# BTConnecter.net
KiCad netlist of a schematic drawn in Altium Designer
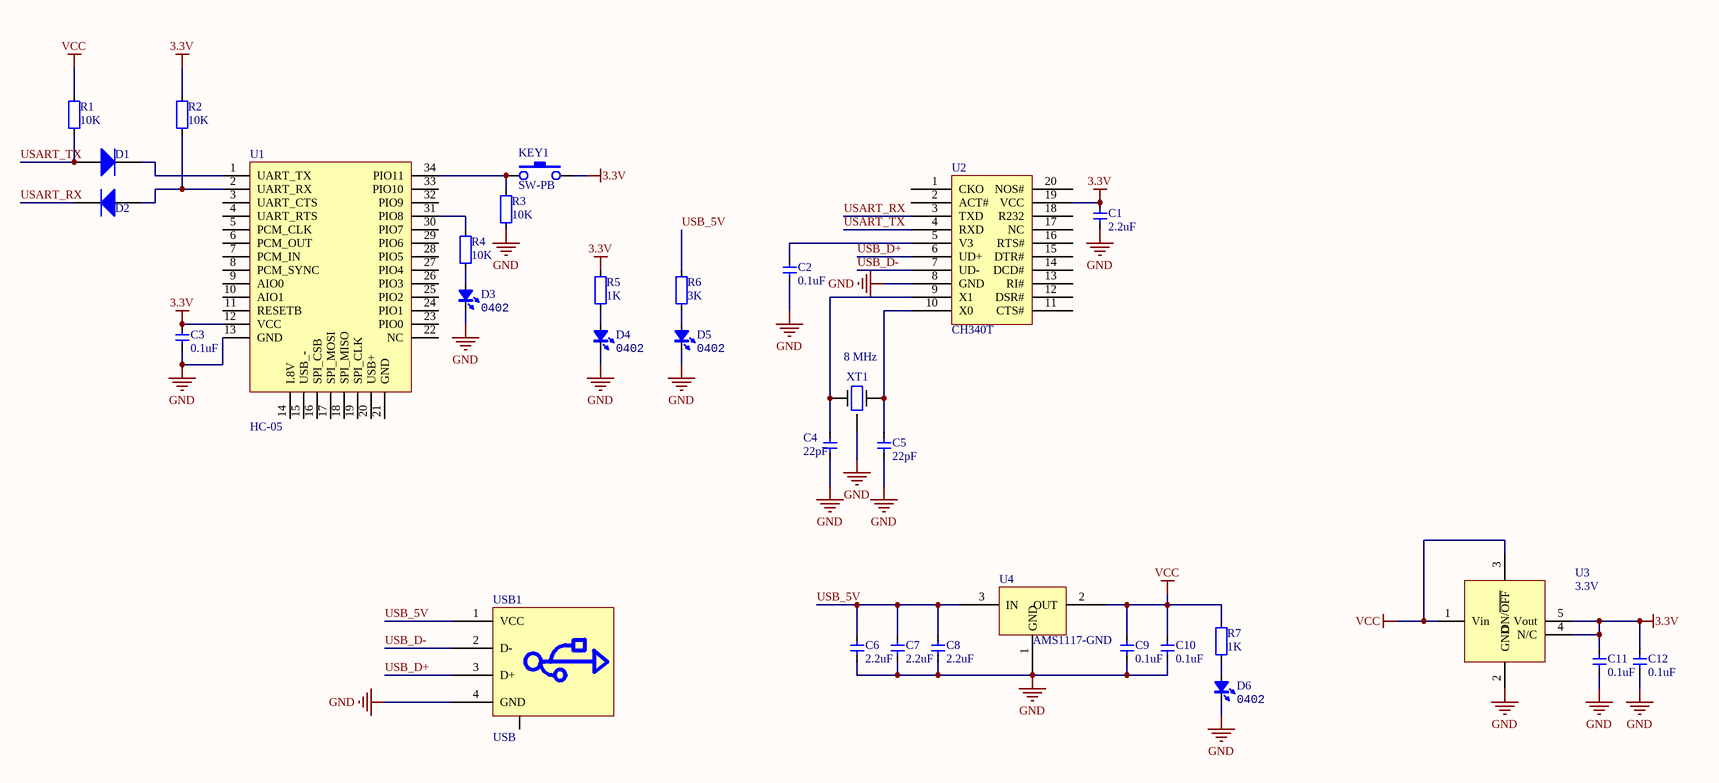
[diagram p0: BTConnecter.SchDoc]

(export (version "E")
  (design (tool "Eeschema 10.0.6"))
  (components
    (comp (ref "C1")
      (value "2.2uF")
      (footprint "CAP_0402")
      (description "Capacitor")
      (libsource (lib "BTConnecter") (part "电容-0402"))
    )
    (comp (ref "C2")
      (value "0.1uF")
      (footprint "CAP_0402")
      (description "Capacitor")
      (libsource (lib "BTConnecter") (part "电容-0402"))
    )
    (comp (ref "C3")
      (value "0.1uF")
      (footprint "CAP_0402")
      (description "Capacitor")
      (libsource (lib "BTConnecter") (part "电容-0402"))
    )
    (comp (ref "C4")
      (value "22pF")
      (footprint "CAP_0402")
      (description "Capacitor")
      (libsource (lib "BTConnecter") (part "电容-0402"))
    )
    (comp (ref "C5")
      (value "22pF")
      (footprint "CAP_0402")
      (description "Capacitor")
      (libsource (lib "BTConnecter") (part "电容-0402"))
    )
    (comp (ref "C6")
      (value "2.2uF")
      (footprint "CAP_0603")
      (description "Capacitor")
      (libsource (lib "BTConnecter") (part "电容-0603"))
    )
    (comp (ref "C7")
      (value "2.2uF")
      (footprint "CAP_0603")
      (description "Capacitor")
      (libsource (lib "BTConnecter") (part "电容-0603"))
    )
    (comp (ref "C8")
      (value "2.2uF")
      (footprint "CAP_0603")
      (description "Capacitor")
      (libsource (lib "BTConnecter") (part "电容-0603"))
    )
    (comp (ref "C9")
      (value "0.1uF")
      (footprint "CAP_0402")
      (description "Capacitor")
      (libsource (lib "BTConnecter") (part "电容-0402"))
    )
    (comp (ref "C10")
      (value "0.1uF")
      (footprint "CAP_0402")
      (description "Capacitor")
      (libsource (lib "BTConnecter") (part "电容-0402"))
    )
    (comp (ref "C11")
      (value "0.1uF")
      (footprint "CAP_0402")
      (description "Capacitor")
      (libsource (lib "BTConnecter") (part "电容-0402"))
    )
    (comp (ref "C12")
      (value "0.1uF")
      (footprint "CAP_0402")
      (description "Capacitor")
      (libsource (lib "BTConnecter") (part "电容-0402"))
    )
    (comp (ref "D1")
      (value "MBR140SFT1G")
      (footprint "DIOM2717X10N")
      (description "Rectifier Diode, Single, 40 V, 1 A, SOD-123FL, 2, 550 mV")
      (libsource (lib "BTConnecter") (part "MBR140SFT1G"))
    )
    (comp (ref "D2")
      (value "MBR140SFT1G")
      (footprint "DIOM2717X10N")
      (description "Rectifier Diode, Single, 40 V, 1 A, SOD-123FL, 2, 550 mV")
      (libsource (lib "BTConnecter") (part "MBR140SFT1G"))
    )
    (comp (ref "D3")
      (value "color?")
      (footprint "LED_0402")
      (description "LED")
      (fields (field (name "TYPE") "0402"))
      (libsource (lib "BTConnecter") (part "LED_0402"))
    )
    (comp (ref "D4")
      (value "color?")
      (footprint "LED_0402")
      (description "LED")
      (fields (field (name "TYPE") "0402"))
      (libsource (lib "BTConnecter") (part "LED_0402"))
    )
    (comp (ref "D5")
      (value "color?")
      (footprint "LED_0402")
      (description "LED")
      (fields (field (name "TYPE") "0402"))
      (libsource (lib "BTConnecter") (part "LED_0402"))
    )
    (comp (ref "D6")
      (value "color?")
      (footprint "LED_0402")
      (description "LED")
      (fields (field (name "TYPE") "0402"))
      (libsource (lib "BTConnecter") (part "LED_0402"))
    )
    (comp (ref "KEY1")
      (value "SW-PB")
      (footprint "ButtonTACT_3x4x2_180H")
      (libsource (lib "BTConnecter") (part "KEY"))
    )
    (comp (ref "R1")
      (value "10K")
      (footprint "RES_0402")
      (description "Resistor")
      (libsource (lib "BTConnecter") (part "电阻-0402"))
    )
    (comp (ref "R2")
      (value "10K")
      (footprint "RES_0402")
      (description "Resistor")
      (libsource (lib "BTConnecter") (part "电阻-0402"))
    )
    (comp (ref "R3")
      (value "10K")
      (footprint "RES_0402")
      (description "Resistor")
      (libsource (lib "BTConnecter") (part "电阻-0402"))
    )
    (comp (ref "R4")
      (value "10K")
      (footprint "RES_0402")
      (description "Resistor")
      (libsource (lib "BTConnecter") (part "电阻-0402"))
    )
    (comp (ref "R5")
      (value "1K")
      (footprint "RES_0402")
      (description "Resistor")
      (libsource (lib "BTConnecter") (part "电阻-0402"))
    )
    (comp (ref "R6")
      (value "3K")
      (footprint "RES_0402")
      (description "Resistor")
      (libsource (lib "BTConnecter") (part "电阻-0402"))
    )
    (comp (ref "R7")
      (value "1K")
      (footprint "RES_0402")
      (description "Resistor")
      (libsource (lib "BTConnecter") (part "电阻-0402"))
    )
    (comp (ref "U1")
      (value "HC-05")
      (footprint "HC-05/06/08V15")
      (libsource (lib "BTConnecter") (part "蓝牙hc05"))
    )
    (comp (ref "U2")
      (value "CH340T")
      (footprint "SSOP-20")
      (description "Port")
      (libsource (lib "BTConnecter") (part "CH340T"))
    )
    (comp (ref "U3")
      (value "3.3V")
      (footprint "SOT23-5")
      (description "IC REG LDO 3.3V 0.25A SOT23-5")
      (fields (field (name "MANUFACTURER") "Texas Instruments"))
      (libsource (lib "BTConnecter") (part "LP5907MFX-3.3/NOPB"))
    )
    (comp (ref "U4")
      (value "AMS1117-GND")
      (footprint "SOT223_JX")
      (description "IC")
      (libsource (lib "BTConnecter") (part "AMS1117-GND"))
    )
    (comp (ref "USB1") (value "USB") (footprint "USB-plug1") (libsource (lib "BTConnecter") (part "USB公头")))
    (comp (ref "XT1")
      (value "8 MHz")
      (footprint "DFN220P320X110-4N")
      (description "Crystal 8MHz ±10ppm 10pF 200 Ohm -10°C ~ 60°C Surface Mount 4-SMD, No Lead (DFN, LCC)")
      (fields
        (field (name "MANUFACTURER") "Abracon LLC")
        (field (name "MANUFACTURER PART NUMBER") "ABM3B-8.000MHZ-10-1-U-T")
      )
      (libsource (lib "BTConnecter") (part "ABM3B-8.000MHZ-10-1-U-T"))
    )
  )
  (nets
    (net (code "1") (name "/USART_RX") (class "Default")
      (node (ref "D2") (pin "K") (pinfunction "K_K") (pintype "passive"))
      (node (ref "U2") (pin "3") (pinfunction "TXD_3") (pintype "passive"))
    )
    (net (code "2") (name "/USART_TX") (class "Default")
      (node (ref "D1") (pin "A") (pinfunction "A_A") (pintype "passive"))
      (node (ref "R1") (pin "1") (pinfunction "1_1") (pintype "passive"))
      (node (ref "U2") (pin "4") (pinfunction "RXD_4") (pintype "passive"))
    )
    (net (code "3") (name "/USB_5V") (class "Default")
      (node (ref "C6") (pin "2") (pinfunction "2_2") (pintype "passive"))
      (node (ref "C7") (pin "2") (pinfunction "2_2") (pintype "passive"))
      (node (ref "C8") (pin "1") (pinfunction "1_1") (pintype "passive"))
      (node (ref "R6") (pin "2") (pinfunction "2_2") (pintype "passive"))
      (node (ref "U4") (pin "3") (pinfunction "IN_3") (pintype "passive"))
      (node (ref "USB1") (pin "1") (pinfunction "VCC_1") (pintype "passive"))
    )
    (net (code "4") (name "/USB_D+") (class "Default")
      (node (ref "U2") (pin "6") (pinfunction "UD+_6") (pintype "passive"))
      (node (ref "USB1") (pin "3") (pinfunction "D+_3") (pintype "passive"))
    )
    (net (code "5") (name "/USB_D-") (class "Default")
      (node (ref "U2") (pin "7") (pinfunction "UD-_7") (pintype "passive"))
      (node (ref "USB1") (pin "2") (pinfunction "D-_2") (pintype "passive"))
    )
    (net (code "6") (name "3.3V") (class "Default")
      (node (ref "C1") (pin "2") (pinfunction "2_2") (pintype "passive"))
      (node (ref "C11") (pin "2") (pinfunction "2_2") (pintype "passive"))
      (node (ref "C12") (pin "2") (pinfunction "2_2") (pintype "passive"))
      (node (ref "C3") (pin "2") (pinfunction "2_2") (pintype "passive"))
      (node (ref "KEY1") (pin "2") (pintype "passive"))
      (node (ref "R2") (pin "2") (pinfunction "2_2") (pintype "passive"))
      (node (ref "R5") (pin "2") (pinfunction "2_2") (pintype "passive"))
      (node (ref "U1") (pin "12") (pinfunction "VCC_12") (pintype "passive"))
      (node (ref "U2") (pin "19") (pinfunction "VCC_19") (pintype "passive"))
      (node (ref "U3") (pin "4") (pinfunction "N/C_4") (pintype "passive"))
      (node (ref "U3") (pin "5") (pinfunction "Vout_5") (pintype "passive"))
    )
    (net (code "7") (name "GND") (class "Default")
      (node (ref "C1") (pin "1") (pinfunction "1_1") (pintype "passive"))
      (node (ref "C10") (pin "1") (pinfunction "1_1") (pintype "passive"))
      (node (ref "C11") (pin "1") (pinfunction "1_1") (pintype "passive"))
      (node (ref "C12") (pin "1") (pinfunction "1_1") (pintype "passive"))
      (node (ref "C2") (pin "1") (pinfunction "1_1") (pintype "passive"))
      (node (ref "C3") (pin "1") (pinfunction "1_1") (pintype "passive"))
      (node (ref "C4") (pin "1") (pinfunction "1_1") (pintype "passive"))
      (node (ref "C5") (pin "1") (pinfunction "1_1") (pintype "passive"))
      (node (ref "C6") (pin "1") (pinfunction "1_1") (pintype "passive"))
      (node (ref "C7") (pin "1") (pinfunction "1_1") (pintype "passive"))
      (node (ref "C8") (pin "2") (pinfunction "2_2") (pintype "passive"))
      (node (ref "C9") (pin "1") (pinfunction "1_1") (pintype "passive"))
      (node (ref "D3") (pin "2") (pinfunction "K_2") (pintype "passive"))
      (node (ref "D4") (pin "2") (pinfunction "K_2") (pintype "passive"))
      (node (ref "D5") (pin "2") (pinfunction "K_2") (pintype "passive"))
      (node (ref "D6") (pin "2") (pinfunction "K_2") (pintype "passive"))
      (node (ref "R3") (pin "1") (pinfunction "1_1") (pintype "passive"))
      (node (ref "U1") (pin "13") (pinfunction "GND_13") (pintype "passive"))
      (node (ref "U2") (pin "8") (pinfunction "GND_8") (pintype "passive"))
      (node (ref "U3") (pin "2") (pinfunction "GND_2") (pintype "passive"))
      (node (ref "U4") (pin "1") (pinfunction "GND_1") (pintype "passive"))
      (node (ref "USB1") (pin "4") (pinfunction "GND_4") (pintype "passive"))
      (node (ref "XT1") (pin "G") (pintype "passive"))
    )
    (net (code "8") (name "Net-(D3-A)") (class "Default")
      (node (ref "D3") (pin "1") (pinfunction "A_1") (pintype "passive"))
      (node (ref "R4") (pin "1") (pinfunction "1_1") (pintype "passive"))
    )
    (net (code "9") (name "Net-(D4-A)") (class "Default")
      (node (ref "D4") (pin "1") (pinfunction "A_1") (pintype "passive"))
      (node (ref "R5") (pin "1") (pinfunction "1_1") (pintype "passive"))
    )
    (net (code "10") (name "Net-(D5-A)") (class "Default")
      (node (ref "D5") (pin "1") (pinfunction "A_1") (pintype "passive"))
      (node (ref "R6") (pin "1") (pinfunction "1_1") (pintype "passive"))
    )
    (net (code "11") (name "Net-(D6-A)") (class "Default")
      (node (ref "D6") (pin "1") (pinfunction "A_1") (pintype "passive"))
      (node (ref "R7") (pin "1") (pinfunction "1_1") (pintype "passive"))
    )
    (net (code "12") (name "Net-(U1-PIO8)") (class "Default")
      (node (ref "R4") (pin "2") (pinfunction "2_2") (pintype "passive"))
      (node (ref "U1") (pin "31") (pinfunction "PIO8_31") (pintype "passive"))
    )
    (net (code "13") (name "Net-(U1-PIO11)") (class "Default")
      (node (ref "KEY1") (pin "1") (pintype "passive"))
      (node (ref "R3") (pin "2") (pinfunction "2_2") (pintype "passive"))
      (node (ref "U1") (pin "34") (pinfunction "PIO11_34") (pintype "passive"))
    )
    (net (code "14") (name "Net-(U1-UART_RX)") (class "Default")
      (node (ref "D2") (pin "A") (pinfunction "A_A") (pintype "passive"))
      (node (ref "R2") (pin "1") (pinfunction "1_1") (pintype "passive"))
      (node (ref "U1") (pin "2") (pinfunction "UART_RX_2") (pintype "passive"))
    )
    (net (code "15") (name "Net-(U1-UART_TX)") (class "Default")
      (node (ref "D1") (pin "K") (pinfunction "K_K") (pintype "passive"))
      (node (ref "U1") (pin "1") (pinfunction "UART_TX_1") (pintype "passive"))
    )
    (net (code "16") (name "Net-(U2-V3)") (class "Default")
      (node (ref "C2") (pin "2") (pinfunction "2_2") (pintype "passive"))
      (node (ref "U2") (pin "5") (pinfunction "V3_5") (pintype "passive"))
    )
    (net (code "17") (name "Net-(U2-X0)") (class "Default")
      (node (ref "C5") (pin "2") (pinfunction "2_2") (pintype "passive"))
      (node (ref "U2") (pin "10") (pinfunction "X0_10") (pintype "passive"))
      (node (ref "XT1") (pin "3") (pintype "passive"))
    )
    (net (code "18") (name "Net-(U2-X1)") (class "Default")
      (node (ref "C4") (pin "2") (pinfunction "2_2") (pintype "passive"))
      (node (ref "U2") (pin "9") (pinfunction "X1_9") (pintype "passive"))
      (node (ref "XT1") (pin "1") (pintype "passive"))
    )
    (net (code "19") (name "VCC") (class "Default")
      (node (ref "C10") (pin "2") (pinfunction "2_2") (pintype "passive"))
      (node (ref "C9") (pin "2") (pinfunction "2_2") (pintype "passive"))
      (node (ref "R1") (pin "2") (pinfunction "2_2") (pintype "passive"))
      (node (ref "R7") (pin "2") (pinfunction "2_2") (pintype "passive"))
      (node (ref "U3") (pin "1") (pinfunction "Vin_1") (pintype "passive"))
      (node (ref "U3") (pin "3") (pinfunction "ON/~{OFF}_3") (pintype "passive"))
      (node (ref "U4") (pin "2") (pinfunction "OUT_2") (pintype "passive"))
    )
    (net (code "20") (name "unconnected-(U1-AIO0-Pad9)") (class "Default")
      (node (ref "U1") (pin "9") (pinfunction "AIO0_9") (pintype "passive"))
    )
    (net (code "21") (name "unconnected-(U1-AIO1-Pad10)") (class "Default")
      (node (ref "U1") (pin "10") (pinfunction "AIO1_10") (pintype "passive"))
    )
    (net (code "22") (name "unconnected-(U1-GND-Pad21)") (class "Default")
      (node (ref "U1") (pin "21") (pinfunction "GND_21") (pintype "passive"))
    )
    (net (code "23") (name "unconnected-(U1-I.8V-Pad14)") (class "Default")
      (node (ref "U1") (pin "14") (pinfunction "I.8V_14") (pintype "passive"))
    )
    (net (code "24") (name "unconnected-(U1-NC-Pad22)") (class "Default")
      (node (ref "U1") (pin "22") (pinfunction "NC_22") (pintype "passive"))
    )
    (net (code "25") (name "unconnected-(U1-PCM_CLK-Pad5)") (class "Default")
      (node (ref "U1") (pin "5") (pinfunction "PCM_CLK_5") (pintype "passive"))
    )
    (net (code "26") (name "unconnected-(U1-PCM_IN-Pad7)") (class "Default")
      (node (ref "U1") (pin "7") (pinfunction "PCM_IN_7") (pintype "passive"))
    )
    (net (code "27") (name "unconnected-(U1-PCM_OUT-Pad6)") (class "Default")
      (node (ref "U1") (pin "6") (pinfunction "PCM_OUT_6") (pintype "passive"))
    )
    (net (code "28") (name "unconnected-(U1-PCM_SYNC-Pad8)") (class "Default")
      (node (ref "U1") (pin "8") (pinfunction "PCM_SYNC_8") (pintype "passive"))
    )
    (net (code "29") (name "unconnected-(U1-PIO0-Pad23)") (class "Default")
      (node (ref "U1") (pin "23") (pinfunction "PIO0_23") (pintype "passive"))
    )
    (net (code "30") (name "unconnected-(U1-PIO1-Pad24)") (class "Default")
      (node (ref "U1") (pin "24") (pinfunction "PIO1_24") (pintype "passive"))
    )
    (net (code "31") (name "unconnected-(U1-PIO2-Pad25)") (class "Default")
      (node (ref "U1") (pin "25") (pinfunction "PIO2_25") (pintype "passive"))
    )
    (net (code "32") (name "unconnected-(U1-PIO3-Pad26)") (class "Default")
      (node (ref "U1") (pin "26") (pinfunction "PIO3_26") (pintype "passive"))
    )
    (net (code "33") (name "unconnected-(U1-PIO4-Pad27)") (class "Default")
      (node (ref "U1") (pin "27") (pinfunction "PIO4_27") (pintype "passive"))
    )
    (net (code "34") (name "unconnected-(U1-PIO5-Pad28)") (class "Default")
      (node (ref "U1") (pin "28") (pinfunction "PIO5_28") (pintype "passive"))
    )
    (net (code "35") (name "unconnected-(U1-PIO6-Pad29)") (class "Default")
      (node (ref "U1") (pin "29") (pinfunction "PIO6_29") (pintype "passive"))
    )
    (net (code "36") (name "unconnected-(U1-PIO7-Pad30)") (class "Default")
      (node (ref "U1") (pin "30") (pinfunction "PIO7_30") (pintype "passive"))
    )
    (net (code "37") (name "unconnected-(U1-PIO9-Pad32)") (class "Default")
      (node (ref "U1") (pin "32") (pinfunction "PIO9_32") (pintype "passive"))
    )
    (net (code "38") (name "unconnected-(U1-PIO10-Pad33)") (class "Default")
      (node (ref "U1") (pin "33") (pinfunction "PIO10_33") (pintype "passive"))
    )
    (net (code "39") (name "unconnected-(U1-RESETB-Pad11)") (class "Default")
      (node (ref "U1") (pin "11") (pinfunction "RESETB_11") (pintype "passive"))
    )
    (net (code "40") (name "unconnected-(U1-SPI_CLK-Pad19)") (class "Default")
      (node (ref "U1") (pin "19") (pinfunction "SPI_CLK_19") (pintype "passive"))
    )
    (net (code "41") (name "unconnected-(U1-SPI_CSB-Pad16)") (class "Default")
      (node (ref "U1") (pin "16") (pinfunction "SPI_CSB_16") (pintype "passive"))
    )
    (net (code "42") (name "unconnected-(U1-SPI_MISO-Pad18)") (class "Default")
      (node (ref "U1") (pin "18") (pinfunction "SPI_MISO_18") (pintype "passive"))
    )
    (net (code "43") (name "unconnected-(U1-SPI_MOSI-Pad17)") (class "Default")
      (node (ref "U1") (pin "17") (pinfunction "SPI_MOSI_17") (pintype "passive"))
    )
    (net (code "44") (name "unconnected-(U1-UART_CTS-Pad3)") (class "Default")
      (node (ref "U1") (pin "3") (pinfunction "UART_CTS_3") (pintype "passive"))
    )
    (net (code "45") (name "unconnected-(U1-UART_RTS-Pad4)") (class "Default")
      (node (ref "U1") (pin "4") (pinfunction "UART_RTS_4") (pintype "passive"))
    )
    (net (code "46") (name "unconnected-(U1-USB+-Pad20)") (class "Default")
      (node (ref "U1") (pin "20") (pinfunction "USB+_20") (pintype "passive"))
    )
    (net (code "47") (name "unconnected-(U1-USB_--Pad15)") (class "Default")
      (node (ref "U1") (pin "15") (pinfunction "USB_-_15") (pintype "passive"))
    )
    (net (code "48") (name "unconnected-(U2-ACT#-Pad2)") (class "Default")
      (node (ref "U2") (pin "2") (pinfunction "ACT#_2") (pintype "passive"))
    )
    (net (code "49") (name "unconnected-(U2-CKO-Pad1)") (class "Default")
      (node (ref "U2") (pin "1") (pinfunction "CKO_1") (pintype "passive"))
    )
    (net (code "50") (name "unconnected-(U2-CTS#-Pad11)") (class "Default")
      (node (ref "U2") (pin "11") (pinfunction "CTS#_11") (pintype "passive"))
    )
    (net (code "51") (name "unconnected-(U2-DCD#-Pad14)") (class "Default")
      (node (ref "U2") (pin "14") (pinfunction "DCD#_14") (pintype "passive"))
    )
    (net (code "52") (name "unconnected-(U2-DSR#-Pad12)") (class "Default")
      (node (ref "U2") (pin "12") (pinfunction "DSR#_12") (pintype "passive"))
    )
    (net (code "53") (name "unconnected-(U2-DTR#-Pad15)") (class "Default")
      (node (ref "U2") (pin "15") (pinfunction "DTR#_15") (pintype "passive"))
    )
    (net (code "54") (name "unconnected-(U2-NC-Pad17)") (class "Default")
      (node (ref "U2") (pin "17") (pinfunction "NC_17") (pintype "passive"))
    )
    (net (code "55") (name "unconnected-(U2-NOS#-Pad20)") (class "Default")
      (node (ref "U2") (pin "20") (pinfunction "NOS#_20") (pintype "passive"))
    )
    (net (code "56") (name "unconnected-(U2-R232-Pad18)") (class "Default")
      (node (ref "U2") (pin "18") (pinfunction "R232_18") (pintype "passive"))
    )
    (net (code "57") (name "unconnected-(U2-RI#-Pad13)") (class "Default")
      (node (ref "U2") (pin "13") (pinfunction "RI#_13") (pintype "passive"))
    )
    (net (code "58") (name "unconnected-(U2-RTS#-Pad16)") (class "Default")
      (node (ref "U2") (pin "16") (pinfunction "RTS#_16") (pintype "passive"))
    )
    (net (code "59") (name "unconnected-(USB1-Pad0)") (class "Default")
      (node (ref "USB1") (pin "0") (pinfunction "0_0") (pintype "passive"))
    )
  )
)
